# main.net
KiCad netlist of a schematic drawn in EAGLE
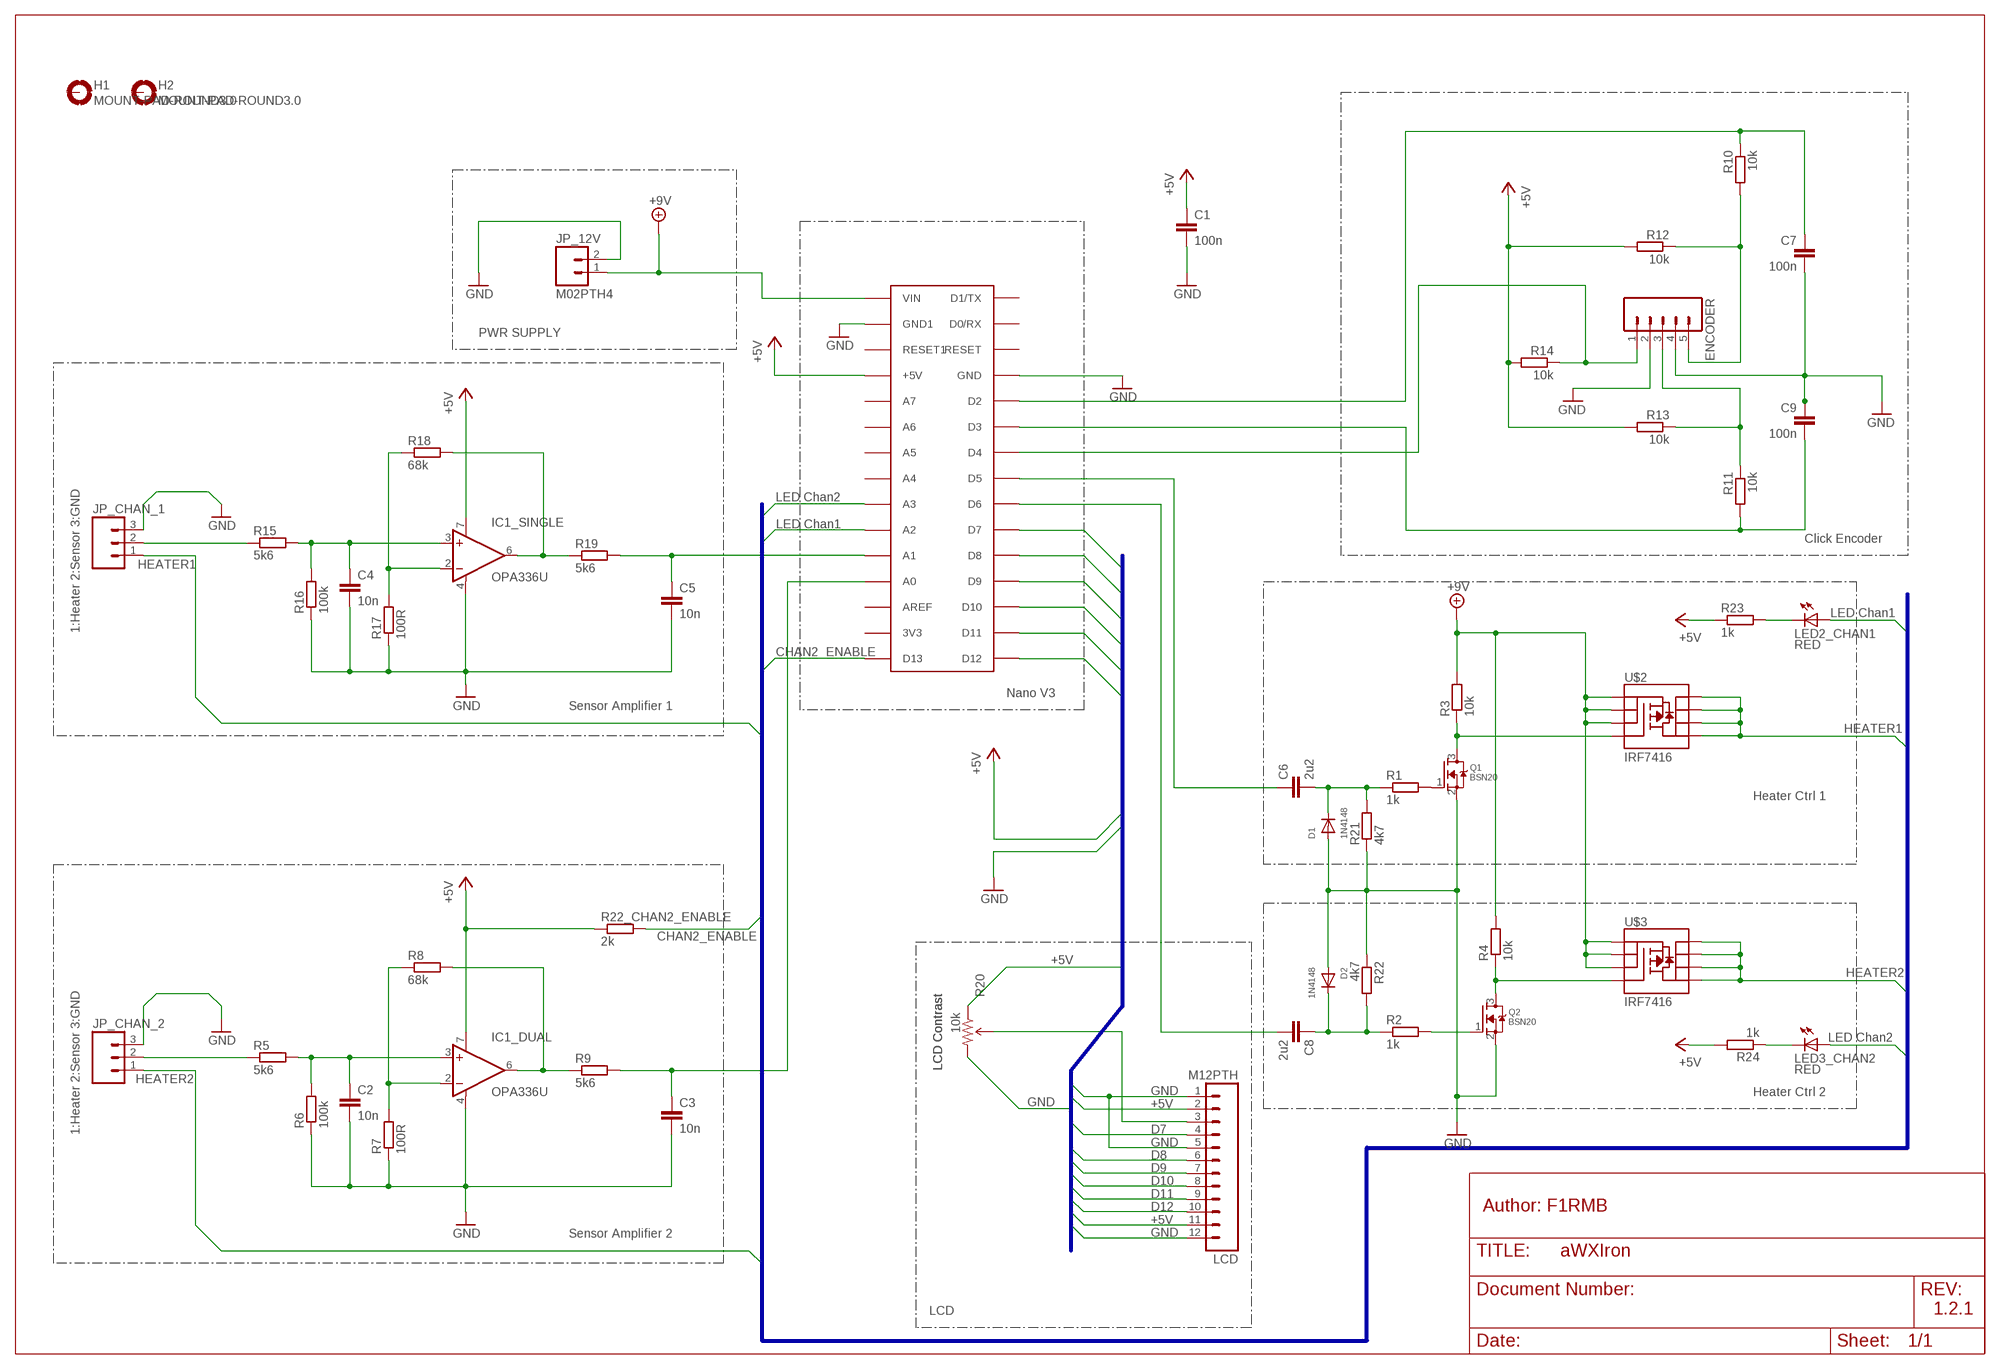
[diagram p0: schematic, sheet 1]

(export (version "E")
  (design (tool "Eeschema 10.0.6"))
  (components
    (comp (ref "C1")
      (value "100n")
      (footprint "eagle-import:C0805")
      (libsource (lib "eagle-import") (part "C-EUC0805"))
    )
    (comp (ref "C2")
      (value "10n")
      (footprint "eagle-import:C0805")
      (libsource (lib "eagle-import") (part "C-EUC0805"))
    )
    (comp (ref "C3")
      (value "10n")
      (footprint "eagle-import:C0805")
      (libsource (lib "eagle-import") (part "C-EUC0805"))
    )
    (comp (ref "C4")
      (value "10n")
      (footprint "eagle-import:C0805")
      (libsource (lib "eagle-import") (part "C-EUC0805"))
    )
    (comp (ref "C5")
      (value "10n")
      (footprint "eagle-import:C0805")
      (libsource (lib "eagle-import") (part "C-EUC0805"))
    )
    (comp (ref "C6")
      (value "2u2")
      (footprint "eagle-import:C0805")
      (libsource (lib "eagle-import") (part "C-EUC0805"))
    )
    (comp (ref "C7")
      (value "100n")
      (footprint "eagle-import:C0805")
      (libsource (lib "eagle-import") (part "C-EUC0805"))
    )
    (comp (ref "C8")
      (value "2u2")
      (footprint "eagle-import:C0805")
      (libsource (lib "eagle-import") (part "C-EUC0805"))
    )
    (comp (ref "C9")
      (value "100n")
      (footprint "eagle-import:C0805")
      (libsource (lib "eagle-import") (part "C-EUC0805"))
    )
    (comp (ref "D1")
      (value "1N4148")
      (footprint "eagle-import:SOD-123")
      (libsource (lib "eagle-import") (part "DIODESOD-123"))
    )
    (comp (ref "D2")
      (value "1N4148")
      (footprint "eagle-import:SOD-123")
      (libsource (lib "eagle-import") (part "DIODESOD-123"))
    )
    (comp (ref "ENCODER")
      (value "M05PTH")
      (footprint "eagle-import:1X05")
      (libsource (lib "eagle-import") (part "M05PTH"))
    )
    (comp (ref "H1")
      (value "MOUNT-PAD-ROUND3.0")
      (footprint "eagle-import:3,0-PAD")
      (libsource (lib "eagle-import") (part "MOUNT-PAD-ROUND3.0"))
    )
    (comp (ref "H2")
      (value "MOUNT-PAD-ROUND3.0")
      (footprint "eagle-import:3,0-PAD")
      (libsource (lib "eagle-import") (part "MOUNT-PAD-ROUND3.0"))
    )
    (comp (ref "IC1_DUAL")
      (value "OPA336U")
      (footprint "eagle-import:SO08")
      (fields (field (name "MF") "TEXAS INSTRUMENT CONNECTORS") (field (name "MPN") "OPA336UA"))
      (libsource (lib "eagle-import") (part "OPA336U"))
    )
    (comp (ref "IC1_SINGLE")
      (value "OPA336U")
      (footprint "eagle-import:SO08")
      (fields (field (name "MF") "TEXAS INSTRUMENT CONNECTORS") (field (name "MPN") "OPA336UA"))
      (libsource (lib "eagle-import") (part "OPA336U"))
    )
    (comp (ref "JP_12V")
      (value "M02PTH4")
      (footprint "eagle-import:1X02_XTRA_BIG")
      (libsource (lib "eagle-import") (part "M02PTH4"))
    )
    (comp (ref "JP_CHAN_1")
      (value "M03SCREW")
      (footprint "eagle-import:SCREWTERMINAL-3.5MM-3")
      (libsource (lib "eagle-import") (part "M03SCREW"))
    )
    (comp (ref "JP_CHAN_2")
      (value "M03SCREW")
      (footprint "eagle-import:SCREWTERMINAL-3.5MM-3")
      (libsource (lib "eagle-import") (part "M03SCREW"))
    )
    (comp (ref "LCD")
      (value "M12PTH")
      (footprint "eagle-import:1X12")
      (libsource (lib "eagle-import") (part "M12PTH"))
    )
    (comp (ref "LED2_CHAN1")
      (value "RED")
      (footprint "eagle-import:LED3MM")
      (libsource (lib "eagle-import") (part "LED3MM"))
    )
    (comp (ref "LED3_CHAN2")
      (value "RED")
      (footprint "eagle-import:LED3MM")
      (libsource (lib "eagle-import") (part "LED3MM"))
    )
    (comp (ref "Q1")
      (value "BSN20")
      (footprint "eagle-import:SOT23")
      (libsource (lib "eagle-import") (part "MOSFET-NREFLOW"))
    )
    (comp (ref "Q2")
      (value "BSN20")
      (footprint "eagle-import:SOT23")
      (libsource (lib "eagle-import") (part "MOSFET-NREFLOW"))
    )
    (comp (ref "R1")
      (value "1k")
      (footprint "eagle-import:R0805")
      (libsource (lib "eagle-import") (part "R-EU_R0805"))
    )
    (comp (ref "R2")
      (value "1k")
      (footprint "eagle-import:R0805")
      (libsource (lib "eagle-import") (part "R-EU_R0805"))
    )
    (comp (ref "R3")
      (value "10k")
      (footprint "eagle-import:R0805")
      (libsource (lib "eagle-import") (part "R-EU_R0805"))
    )
    (comp (ref "R4")
      (value "10k")
      (footprint "eagle-import:R0805")
      (libsource (lib "eagle-import") (part "R-EU_R0805"))
    )
    (comp (ref "R5")
      (value "5k6")
      (footprint "eagle-import:R0805")
      (libsource (lib "eagle-import") (part "R-EU_R0805"))
    )
    (comp (ref "R6")
      (value "100k")
      (footprint "eagle-import:R0805")
      (libsource (lib "eagle-import") (part "R-EU_R0805"))
    )
    (comp (ref "R7")
      (value "100R")
      (footprint "eagle-import:R0805")
      (libsource (lib "eagle-import") (part "R-EU_R0805"))
    )
    (comp (ref "R8")
      (value "68k")
      (footprint "eagle-import:R0805")
      (libsource (lib "eagle-import") (part "R-EU_R0805"))
    )
    (comp (ref "R9")
      (value "5k6")
      (footprint "eagle-import:R0805")
      (libsource (lib "eagle-import") (part "R-EU_R0805"))
    )
    (comp (ref "R10")
      (value "10k")
      (footprint "eagle-import:R0805")
      (libsource (lib "eagle-import") (part "R-EU_R0805"))
    )
    (comp (ref "R11")
      (value "10k")
      (footprint "eagle-import:R0805")
      (libsource (lib "eagle-import") (part "R-EU_R0805"))
    )
    (comp (ref "R12")
      (value "10k")
      (footprint "eagle-import:R0805")
      (libsource (lib "eagle-import") (part "R-EU_R0805"))
    )
    (comp (ref "R13")
      (value "10k")
      (footprint "eagle-import:R0805")
      (libsource (lib "eagle-import") (part "R-EU_R0805"))
    )
    (comp (ref "R14")
      (value "10k")
      (footprint "eagle-import:R0805")
      (libsource (lib "eagle-import") (part "R-EU_R0805"))
    )
    (comp (ref "R15")
      (value "5k6")
      (footprint "eagle-import:R0805")
      (libsource (lib "eagle-import") (part "R-EU_R0805"))
    )
    (comp (ref "R16")
      (value "100k")
      (footprint "eagle-import:R0805")
      (libsource (lib "eagle-import") (part "R-EU_R0805"))
    )
    (comp (ref "R17")
      (value "100R")
      (footprint "eagle-import:R0805")
      (libsource (lib "eagle-import") (part "R-EU_R0805"))
    )
    (comp (ref "R18")
      (value "68k")
      (footprint "eagle-import:R0805")
      (libsource (lib "eagle-import") (part "R-EU_R0805"))
    )
    (comp (ref "R19")
      (value "5k6")
      (footprint "eagle-import:R0805")
      (libsource (lib "eagle-import") (part "R-EU_R0805"))
    )
    (comp (ref "R20")
      (value "10k")
      (footprint "eagle-import:3362U-2")
      (libsource (lib "eagle-import") (part "TRIMPOT3362U-2"))
    )
    (comp (ref "R21")
      (value "4k7")
      (footprint "eagle-import:R0805")
      (libsource (lib "eagle-import") (part "R-EU_R0805"))
    )
    (comp (ref "R22")
      (value "4k7")
      (footprint "eagle-import:R0805")
      (libsource (lib "eagle-import") (part "R-EU_R0805"))
    )
    (comp (ref "R22_CHAN2_ENABLE")
      (value "2k")
      (footprint "eagle-import:R0805")
      (libsource (lib "eagle-import") (part "R-EU_R0805"))
    )
    (comp (ref "R23")
      (value "1k")
      (footprint "eagle-import:R0805")
      (libsource (lib "eagle-import") (part "R-EU_R0805"))
    )
    (comp (ref "R24")
      (value "1k")
      (footprint "eagle-import:R0805")
      (libsource (lib "eagle-import") (part "R-EU_R0805"))
    )
    (comp (ref "U$1")
      (value "ARDUINONANO")
      (footprint "eagle-import:PDIP-32")
      (libsource (lib "eagle-import") (part "ARDUINONANO"))
    )
    (comp (ref "U$2")
      (value "IRF7416")
      (footprint "eagle-import:SO08")
      (libsource (lib "eagle-import") (part "MOSFET-PCHANNEL-SOIC8SOIC8"))
    )
    (comp (ref "U$3")
      (value "IRF7416")
      (footprint "eagle-import:SO08")
      (libsource (lib "eagle-import") (part "MOSFET-PCHANNEL-SOIC8SOIC8"))
    )
  )
  (nets
    (net (code "1") (name "+5V") (class "Default")
      (node (ref "C1") (pin "1") (pinfunction "1_1") (pintype "passive"))
      (node (ref "IC1_DUAL") (pin "7") (pinfunction "V+_7") (pintype "power_in"))
      (node (ref "IC1_SINGLE") (pin "7") (pinfunction "V+_7") (pintype "power_in"))
      (node (ref "LCD") (pin "11") (pinfunction "11_11") (pintype "passive"))
      (node (ref "LCD") (pin "2") (pinfunction "2_2") (pintype "passive"))
      (node (ref "R12") (pin "2") (pinfunction "2_2") (pintype "passive"))
      (node (ref "R13") (pin "2") (pinfunction "2_2") (pintype "passive"))
      (node (ref "R14") (pin "2") (pinfunction "2_2") (pintype "passive"))
      (node (ref "R20") (pin "1") (pinfunction "CCW_1") (pintype "passive"))
      (node (ref "R22_CHAN2_ENABLE") (pin "1") (pinfunction "1_1") (pintype "passive"))
      (node (ref "R23") (pin "1") (pinfunction "1_1") (pintype "passive"))
      (node (ref "R24") (pin "2") (pinfunction "2_2") (pintype "passive"))
      (node (ref "U$1") (pin "+5V") (pinfunction "+5V_+5V") (pintype "bidirectional"))
    )
    (net (code "2") (name "+9V") (class "Default")
      (node (ref "JP_12V") (pin "1") (pinfunction "1_1") (pintype "passive"))
      (node (ref "R3") (pin "2") (pinfunction "2_2") (pintype "passive"))
      (node (ref "R4") (pin "2") (pinfunction "2_2") (pintype "passive"))
      (node (ref "U$1") (pin "VIN") (pinfunction "VIN_VIN") (pintype "bidirectional"))
      (node (ref "U$2") (pin "1") (pinfunction "S_1") (pintype "bidirectional"))
      (node (ref "U$2") (pin "2") (pinfunction "S_2") (pintype "bidirectional"))
      (node (ref "U$2") (pin "3") (pinfunction "S_3") (pintype "bidirectional"))
      (node (ref "U$3") (pin "1") (pinfunction "S_1") (pintype "bidirectional"))
      (node (ref "U$3") (pin "2") (pinfunction "S_2") (pintype "bidirectional"))
      (node (ref "U$3") (pin "3") (pinfunction "S_3") (pintype "bidirectional"))
    )
    (net (code "3") (name "/DB4") (class "Default")
      (node (ref "LCD") (pin "7") (pinfunction "7_7") (pintype "passive"))
      (node (ref "U$1") (pin "D9") (pinfunction "D9_D9") (pintype "bidirectional"))
    )
    (net (code "4") (name "/DB5") (class "Default")
      (node (ref "LCD") (pin "8") (pinfunction "8_8") (pintype "passive"))
      (node (ref "U$1") (pin "D10") (pinfunction "D10_D10") (pintype "bidirectional"))
    )
    (net (code "5") (name "/DB6") (class "Default")
      (node (ref "LCD") (pin "9") (pinfunction "9_9") (pintype "passive"))
      (node (ref "U$1") (pin "D11") (pinfunction "D11_D11") (pintype "bidirectional"))
    )
    (net (code "6") (name "/DB7") (class "Default")
      (node (ref "LCD") (pin "10") (pinfunction "10_10") (pintype "passive"))
      (node (ref "U$1") (pin "D12") (pinfunction "D12_D12") (pintype "bidirectional"))
    )
    (net (code "7") (name "/E") (class "Default")
      (node (ref "LCD") (pin "6") (pinfunction "6_6") (pintype "passive"))
      (node (ref "U$1") (pin "D8") (pinfunction "D8_D8") (pintype "bidirectional"))
    )
    (net (code "8") (name "/ENABLECHAN2") (class "Default")
      (node (ref "R22_CHAN2_ENABLE") (pin "2") (pinfunction "2_2") (pintype "passive"))
      (node (ref "U$1") (pin "D13") (pinfunction "D13_D13") (pintype "bidirectional"))
    )
    (net (code "9") (name "/HEATCHAN1") (class "Default")
      (node (ref "LED2_CHAN1") (pin "A") (pinfunction "A_A") (pintype "passive"))
      (node (ref "U$1") (pin "A2") (pinfunction "A2_A2") (pintype "bidirectional"))
    )
    (net (code "10") (name "/HEATCHAN2") (class "Default")
      (node (ref "LED3_CHAN2") (pin "A") (pinfunction "A_A") (pintype "passive"))
      (node (ref "U$1") (pin "A3") (pinfunction "A3_A3") (pintype "bidirectional"))
    )
    (net (code "11") (name "/HEATER1") (class "Default")
      (node (ref "JP_CHAN_1") (pin "1") (pinfunction "1_1") (pintype "passive"))
      (node (ref "U$2") (pin "5") (pinfunction "D_5") (pintype "bidirectional"))
      (node (ref "U$2") (pin "6") (pinfunction "D_6") (pintype "bidirectional"))
      (node (ref "U$2") (pin "7") (pinfunction "D_7") (pintype "bidirectional"))
      (node (ref "U$2") (pin "8") (pinfunction "D_8") (pintype "bidirectional"))
    )
    (net (code "12") (name "/HEATER2") (class "Default")
      (node (ref "JP_CHAN_2") (pin "1") (pinfunction "1_1") (pintype "passive"))
      (node (ref "U$3") (pin "5") (pinfunction "D_5") (pintype "bidirectional"))
      (node (ref "U$3") (pin "6") (pinfunction "D_6") (pintype "bidirectional"))
      (node (ref "U$3") (pin "7") (pinfunction "D_7") (pintype "bidirectional"))
      (node (ref "U$3") (pin "8") (pinfunction "D_8") (pintype "bidirectional"))
    )
    (net (code "13") (name "/RS") (class "Default")
      (node (ref "LCD") (pin "4") (pinfunction "4_4") (pintype "passive"))
      (node (ref "U$1") (pin "D7") (pinfunction "D7_D7") (pintype "bidirectional"))
    )
    (net (code "14") (name "GND") (class "Default")
      (node (ref "C1") (pin "2") (pinfunction "2_2") (pintype "passive"))
      (node (ref "C2") (pin "2") (pinfunction "2_2") (pintype "passive"))
      (node (ref "C3") (pin "2") (pinfunction "2_2") (pintype "passive"))
      (node (ref "C4") (pin "2") (pinfunction "2_2") (pintype "passive"))
      (node (ref "C5") (pin "2") (pinfunction "2_2") (pintype "passive"))
      (node (ref "C7") (pin "2") (pinfunction "2_2") (pintype "passive"))
      (node (ref "C9") (pin "1") (pinfunction "1_1") (pintype "passive"))
      (node (ref "D1") (pin "A") (pinfunction "A_A") (pintype "passive"))
      (node (ref "D2") (pin "A") (pinfunction "A_A") (pintype "passive"))
      (node (ref "ENCODER") (pin "2") (pinfunction "2_2") (pintype "passive"))
      (node (ref "ENCODER") (pin "4") (pinfunction "4_4") (pintype "passive"))
      (node (ref "IC1_DUAL") (pin "4") (pinfunction "V-_4") (pintype "power_in"))
      (node (ref "IC1_SINGLE") (pin "4") (pinfunction "V-_4") (pintype "power_in"))
      (node (ref "JP_12V") (pin "2") (pinfunction "2_2") (pintype "passive"))
      (node (ref "JP_CHAN_1") (pin "3") (pinfunction "3_3") (pintype "passive"))
      (node (ref "JP_CHAN_2") (pin "3") (pinfunction "3_3") (pintype "passive"))
      (node (ref "LCD") (pin "1") (pinfunction "1_1") (pintype "passive"))
      (node (ref "LCD") (pin "12") (pinfunction "12_12") (pintype "passive"))
      (node (ref "LCD") (pin "5") (pinfunction "5_5") (pintype "passive"))
      (node (ref "Q1") (pin "2") (pinfunction "S_2") (pintype "bidirectional"))
      (node (ref "Q2") (pin "2") (pinfunction "S_2") (pintype "bidirectional"))
      (node (ref "R16") (pin "1") (pinfunction "1_1") (pintype "passive"))
      (node (ref "R17") (pin "1") (pinfunction "1_1") (pintype "passive"))
      (node (ref "R20") (pin "3") (pinfunction "CW_3") (pintype "passive"))
      (node (ref "R21") (pin "1") (pinfunction "1_1") (pintype "passive"))
      (node (ref "R22") (pin "1") (pinfunction "1_1") (pintype "passive"))
      (node (ref "R6") (pin "1") (pinfunction "1_1") (pintype "passive"))
      (node (ref "R7") (pin "1") (pinfunction "1_1") (pintype "passive"))
      (node (ref "U$1") (pin "GND") (pinfunction "GND_GND") (pintype "bidirectional"))
      (node (ref "U$1") (pin "GND1") (pinfunction "GND1_GND1") (pintype "bidirectional"))
    )
    (net (code "15") (name "Net-(C3-Pad1)") (class "Default")
      (node (ref "C3") (pin "1") (pinfunction "1_1") (pintype "passive"))
      (node (ref "R9") (pin "2") (pinfunction "2_2") (pintype "passive"))
      (node (ref "U$1") (pin "A0") (pinfunction "A0_A0") (pintype "bidirectional"))
    )
    (net (code "16") (name "Net-(C5-Pad1)") (class "Default")
      (node (ref "C5") (pin "1") (pinfunction "1_1") (pintype "passive"))
      (node (ref "R19") (pin "2") (pinfunction "2_2") (pintype "passive"))
      (node (ref "U$1") (pin "A1") (pinfunction "A1_A1") (pintype "bidirectional"))
    )
    (net (code "17") (name "Net-(C6-Pad1)") (class "Default")
      (node (ref "C6") (pin "1") (pinfunction "1_1") (pintype "passive"))
      (node (ref "U$1") (pin "D5") (pinfunction "D5_D5") (pintype "bidirectional"))
    )
    (net (code "18") (name "Net-(C6-Pad2)") (class "Default")
      (node (ref "C6") (pin "2") (pinfunction "2_2") (pintype "passive"))
      (node (ref "D1") (pin "C") (pinfunction "C_C") (pintype "passive"))
      (node (ref "R1") (pin "1") (pinfunction "1_1") (pintype "passive"))
      (node (ref "R21") (pin "2") (pinfunction "2_2") (pintype "passive"))
    )
    (net (code "19") (name "Net-(C7-Pad1)") (class "Default")
      (node (ref "C7") (pin "1") (pinfunction "1_1") (pintype "passive"))
      (node (ref "R10") (pin "1") (pinfunction "1_1") (pintype "passive"))
      (node (ref "U$1") (pin "D2") (pinfunction "D2_D2") (pintype "bidirectional"))
    )
    (net (code "20") (name "Net-(C8-Pad1)") (class "Default")
      (node (ref "C8") (pin "1") (pinfunction "1_1") (pintype "passive"))
      (node (ref "D2") (pin "C") (pinfunction "C_C") (pintype "passive"))
      (node (ref "R2") (pin "1") (pinfunction "1_1") (pintype "passive"))
      (node (ref "R22") (pin "2") (pinfunction "2_2") (pintype "passive"))
    )
    (net (code "21") (name "Net-(C8-Pad2)") (class "Default")
      (node (ref "C8") (pin "2") (pinfunction "2_2") (pintype "passive"))
      (node (ref "U$1") (pin "D6") (pinfunction "D6_D6") (pintype "bidirectional"))
    )
    (net (code "22") (name "Net-(C9-Pad2)") (class "Default")
      (node (ref "C9") (pin "2") (pinfunction "2_2") (pintype "passive"))
      (node (ref "R11") (pin "2") (pinfunction "2_2") (pintype "passive"))
      (node (ref "U$1") (pin "D3") (pinfunction "D3_D3") (pintype "bidirectional"))
    )
    (net (code "23") (name "Net-(ENCODER-Pad1)") (class "Default")
      (node (ref "ENCODER") (pin "1") (pinfunction "1_1") (pintype "passive"))
      (node (ref "R14") (pin "1") (pinfunction "1_1") (pintype "passive"))
      (node (ref "U$1") (pin "D4") (pinfunction "D4_D4") (pintype "bidirectional"))
    )
    (net (code "24") (name "Net-(ENCODER-Pad3)") (class "Default")
      (node (ref "ENCODER") (pin "3") (pinfunction "3_3") (pintype "passive"))
      (node (ref "R11") (pin "1") (pinfunction "1_1") (pintype "passive"))
      (node (ref "R13") (pin "1") (pinfunction "1_1") (pintype "passive"))
    )
    (net (code "25") (name "Net-(ENCODER-Pad5)") (class "Default")
      (node (ref "ENCODER") (pin "5") (pinfunction "5_5") (pintype "passive"))
      (node (ref "R10") (pin "2") (pinfunction "2_2") (pintype "passive"))
      (node (ref "R12") (pin "1") (pinfunction "1_1") (pintype "passive"))
    )
    (net (code "26") (name "Net-(IC1_DUAL-+IN)") (class "Default")
      (node (ref "C2") (pin "1") (pinfunction "1_1") (pintype "passive"))
      (node (ref "IC1_DUAL") (pin "3") (pinfunction "+IN_3") (pintype "input"))
      (node (ref "R5") (pin "2") (pinfunction "2_2") (pintype "passive"))
      (node (ref "R6") (pin "2") (pinfunction "2_2") (pintype "passive"))
    )
    (net (code "27") (name "Net-(IC1_DUAL--IN)") (class "Default")
      (node (ref "IC1_DUAL") (pin "2") (pinfunction "-IN_2") (pintype "input"))
      (node (ref "R7") (pin "2") (pinfunction "2_2") (pintype "passive"))
      (node (ref "R8") (pin "1") (pinfunction "1_1") (pintype "passive"))
    )
    (net (code "28") (name "Net-(IC1_DUAL-OUT)") (class "Default")
      (node (ref "IC1_DUAL") (pin "6") (pinfunction "OUT_6") (pintype "output"))
      (node (ref "R8") (pin "2") (pinfunction "2_2") (pintype "passive"))
      (node (ref "R9") (pin "1") (pinfunction "1_1") (pintype "passive"))
    )
    (net (code "29") (name "Net-(IC1_SINGLE-+IN)") (class "Default")
      (node (ref "C4") (pin "1") (pinfunction "1_1") (pintype "passive"))
      (node (ref "IC1_SINGLE") (pin "3") (pinfunction "+IN_3") (pintype "input"))
      (node (ref "R15") (pin "2") (pinfunction "2_2") (pintype "passive"))
      (node (ref "R16") (pin "2") (pinfunction "2_2") (pintype "passive"))
    )
    (net (code "30") (name "Net-(IC1_SINGLE--IN)") (class "Default")
      (node (ref "IC1_SINGLE") (pin "2") (pinfunction "-IN_2") (pintype "input"))
      (node (ref "R17") (pin "2") (pinfunction "2_2") (pintype "passive"))
      (node (ref "R18") (pin "1") (pinfunction "1_1") (pintype "passive"))
    )
    (net (code "31") (name "Net-(IC1_SINGLE-OUT)") (class "Default")
      (node (ref "IC1_SINGLE") (pin "6") (pinfunction "OUT_6") (pintype "output"))
      (node (ref "R18") (pin "2") (pinfunction "2_2") (pintype "passive"))
      (node (ref "R19") (pin "1") (pinfunction "1_1") (pintype "passive"))
    )
    (net (code "32") (name "Net-(JP_CHAN_1-Pad2)") (class "Default")
      (node (ref "JP_CHAN_1") (pin "2") (pinfunction "2_2") (pintype "passive"))
      (node (ref "R15") (pin "1") (pinfunction "1_1") (pintype "passive"))
    )
    (net (code "33") (name "Net-(JP_CHAN_2-Pad2)") (class "Default")
      (node (ref "JP_CHAN_2") (pin "2") (pinfunction "2_2") (pintype "passive"))
      (node (ref "R5") (pin "1") (pinfunction "1_1") (pintype "passive"))
    )
    (net (code "34") (name "Net-(LED2_CHAN1-C)") (class "Default")
      (node (ref "LED2_CHAN1") (pin "K") (pinfunction "C_K") (pintype "passive"))
      (node (ref "R23") (pin "2") (pinfunction "2_2") (pintype "passive"))
    )
    (net (code "35") (name "Net-(LED3_CHAN2-C)") (class "Default")
      (node (ref "LED3_CHAN2") (pin "K") (pinfunction "C_K") (pintype "passive"))
      (node (ref "R24") (pin "1") (pinfunction "1_1") (pintype "passive"))
    )
    (net (code "36") (name "Net-(Q1-D)") (class "Default")
      (node (ref "Q1") (pin "3") (pinfunction "D_3") (pintype "bidirectional"))
      (node (ref "R3") (pin "1") (pinfunction "1_1") (pintype "passive"))
      (node (ref "U$2") (pin "4") (pinfunction "G_4") (pintype "bidirectional"))
    )
    (net (code "37") (name "Net-(Q1-G)") (class "Default")
      (node (ref "Q1") (pin "1") (pinfunction "G_1") (pintype "bidirectional"))
      (node (ref "R1") (pin "2") (pinfunction "2_2") (pintype "passive"))
    )
    (net (code "38") (name "Net-(Q2-D)") (class "Default")
      (node (ref "Q2") (pin "3") (pinfunction "D_3") (pintype "bidirectional"))
      (node (ref "R4") (pin "1") (pinfunction "1_1") (pintype "passive"))
      (node (ref "U$3") (pin "4") (pinfunction "G_4") (pintype "bidirectional"))
    )
    (net (code "39") (name "Net-(Q2-G)") (class "Default")
      (node (ref "Q2") (pin "1") (pinfunction "G_1") (pintype "bidirectional"))
      (node (ref "R2") (pin "2") (pinfunction "2_2") (pintype "passive"))
    )
    (net (code "40") (name "Net-(R20-WIPER)") (class "Default")
      (node (ref "LCD") (pin "3") (pinfunction "3_3") (pintype "passive"))
      (node (ref "R20") (pin "2") (pinfunction "WIPER_2") (pintype "passive"))
    )
    (net (code "41") (name "unconnected-(H1-MOUNT-PadB3,0)") (class "Default")
      (node (ref "H1") (pin "B3,0") (pinfunction "MOUNT_B3,0") (pintype "passive"))
    )
    (net (code "42") (name "unconnected-(H2-MOUNT-PadB3,0)") (class "Default")
      (node (ref "H2") (pin "B3,0") (pinfunction "MOUNT_B3,0") (pintype "passive"))
    )
    (net (code "43") (name "unconnected-(U$1-Pad3V3)") (class "Default")
      (node (ref "U$1") (pin "3V3") (pinfunction "3V3_3V3") (pintype "bidirectional"))
    )
    (net (code "44") (name "unconnected-(U$1-PadA4)") (class "Default")
      (node (ref "U$1") (pin "A4") (pinfunction "A4_A4") (pintype "bidirectional"))
    )
    (net (code "45") (name "unconnected-(U$1-PadA5)") (class "Default")
      (node (ref "U$1") (pin "A5") (pinfunction "A5_A5") (pintype "bidirectional"))
    )
    (net (code "46") (name "unconnected-(U$1-PadA6)") (class "Default")
      (node (ref "U$1") (pin "A6") (pinfunction "A6_A6") (pintype "bidirectional"))
    )
    (net (code "47") (name "unconnected-(U$1-PadA7)") (class "Default")
      (node (ref "U$1") (pin "A7") (pinfunction "A7_A7") (pintype "bidirectional"))
    )
    (net (code "48") (name "unconnected-(U$1-PadAREF)") (class "Default")
      (node (ref "U$1") (pin "AREF") (pinfunction "AREF_AREF") (pintype "bidirectional"))
    )
    (net (code "49") (name "unconnected-(U$1-PadD0{slash}RX)") (class "Default")
      (node (ref "U$1") (pin "D0/RX") (pinfunction "D0/RX_D0/RX") (pintype "bidirectional"))
    )
    (net (code "50") (name "unconnected-(U$1-PadD1{slash}TX)") (class "Default")
      (node (ref "U$1") (pin "D1/TX") (pinfunction "D1/TX_D1/TX") (pintype "bidirectional"))
    )
    (net (code "51") (name "unconnected-(U$1-PadRESET)") (class "Default")
      (node (ref "U$1") (pin "RESET") (pinfunction "RESET_RESET") (pintype "bidirectional"))
    )
    (net (code "52") (name "unconnected-(U$1-PadRESET1)") (class "Default")
      (node (ref "U$1") (pin "RESET1") (pinfunction "RESET1_RESET1") (pintype "bidirectional"))
    )
  )
)
